# BBeams.net
KiCad netlist of a schematic drawn in Altium Designer
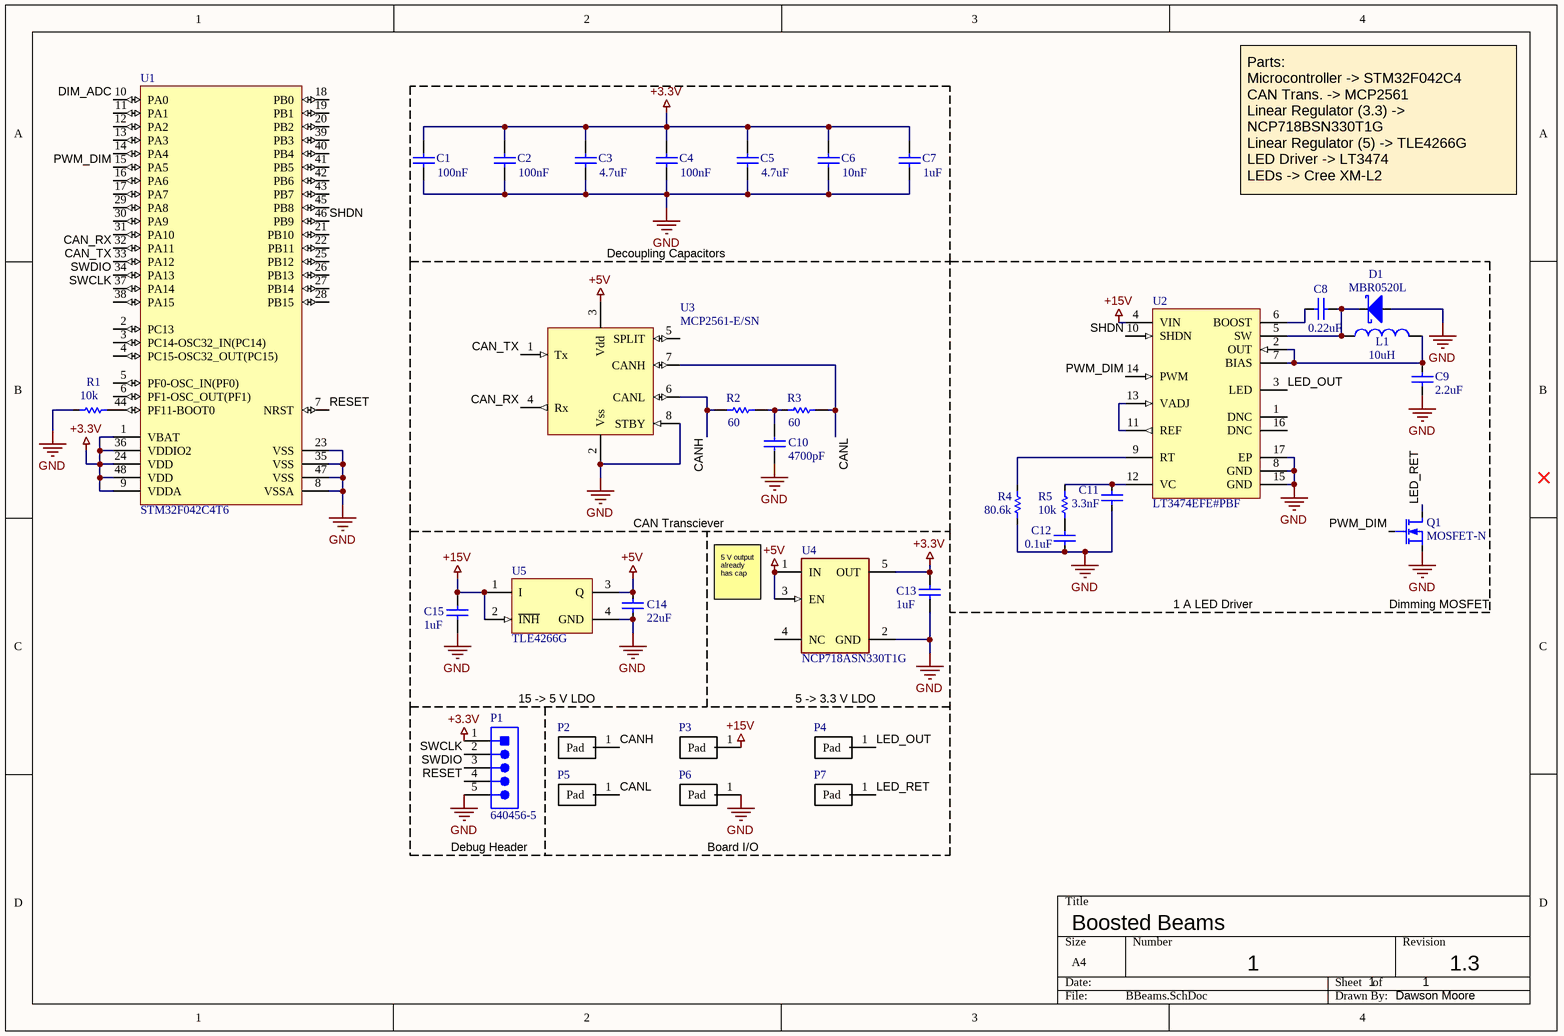
[diagram p0: BBeams.SchDoc]

(export (version "E")
  (design (tool "Eeschema 10.0.6"))
  (components
    (comp (ref "C1")
      (value "100nF")
      (footprint "1608[0603]")
      (description "Capacitor (Semiconductor SIM Model)")
      (fields (field (name "Comment") "Cap Semi") (field (name "PUBLISHER") "Altium Limited"))
      (libsource (lib "Miscellaneous Devices") (part "Cap Semi"))
    )
    (comp (ref "C2")
      (value "100nF")
      (footprint "1608[0603]")
      (description "Capacitor (Semiconductor SIM Model)")
      (fields (field (name "Comment") "Cap Semi") (field (name "PUBLISHER") "Altium Limited"))
      (libsource (lib "Miscellaneous Devices") (part "Cap Semi"))
    )
    (comp (ref "C3")
      (value "4.7uF")
      (footprint "1608[0603]")
      (description "Capacitor (Semiconductor SIM Model)")
      (fields (field (name "Comment") "Cap Semi") (field (name "PUBLISHER") "Altium Limited"))
      (libsource (lib "Miscellaneous Devices") (part "Cap Semi"))
    )
    (comp (ref "C4")
      (value "100nF")
      (footprint "1608[0603]")
      (description "Capacitor (Semiconductor SIM Model)")
      (fields (field (name "Comment") "Cap Semi") (field (name "PUBLISHER") "Altium Limited"))
      (libsource (lib "Miscellaneous Devices") (part "Cap Semi"))
    )
    (comp (ref "C5")
      (value "4.7uF")
      (footprint "1608[0603]")
      (description "Capacitor (Semiconductor SIM Model)")
      (fields (field (name "Comment") "Cap Semi") (field (name "PUBLISHER") "Altium Limited"))
      (libsource (lib "Miscellaneous Devices") (part "Cap Semi"))
    )
    (comp (ref "C6")
      (value "10nF")
      (footprint "1608[0603]")
      (description "Capacitor (Semiconductor SIM Model)")
      (fields (field (name "Comment") "Cap Semi") (field (name "PUBLISHER") "Altium Limited"))
      (libsource (lib "Miscellaneous Devices") (part "Cap Semi"))
    )
    (comp (ref "C7")
      (value "1uF")
      (footprint "1608[0603]")
      (description "Capacitor (Semiconductor SIM Model)")
      (fields (field (name "Comment") "Cap Semi") (field (name "PUBLISHER") "Altium Limited"))
      (libsource (lib "Miscellaneous Devices") (part "Cap Semi"))
    )
    (comp (ref "C8")
      (value "0.22uF")
      (footprint "1608[0603]")
      (description "Capacitor (Semiconductor SIM Model)")
      (fields (field (name "Comment") "Cap Semi") (field (name "PUBLISHER") "Altium Limited"))
      (libsource (lib "") (part "Cap Semi_1"))
    )
    (comp (ref "C9")
      (value "2.2uF")
      (footprint "1608[0603]")
      (description "Capacitor (Semiconductor SIM Model)")
      (fields (field (name "Comment") "Cap Semi") (field (name "PUBLISHER") "Altium Limited"))
      (libsource (lib "") (part "Cap Semi_1"))
    )
    (comp (ref "C10")
      (value "4700pF")
      (footprint "1608[0603]")
      (description "Capacitor (Semiconductor SIM Model)")
      (fields (field (name "Comment") "Cap Semi") (field (name "PUBLISHER") "Altium Limited"))
      (libsource (lib "Miscellaneous Devices") (part "Cap Semi"))
    )
    (comp (ref "C11")
      (value "3.3nF")
      (footprint "1608[0603]")
      (description "Capacitor (Semiconductor SIM Model)")
      (fields (field (name "Comment") "Cap Semi") (field (name "PUBLISHER") "Altium Limited"))
      (libsource (lib "") (part "Cap Semi_2"))
    )
    (comp (ref "C12")
      (value "0.1uF")
      (footprint "1608[0603]")
      (description "Capacitor (Semiconductor SIM Model)")
      (fields (field (name "Comment") "Cap Semi") (field (name "PUBLISHER") "Altium Limited"))
      (libsource (lib "") (part "Cap Semi_2"))
    )
    (comp (ref "C13")
      (value "1uF")
      (footprint "1608[0603]")
      (description "Capacitor (Semiconductor SIM Model)")
      (fields (field (name "Comment") "Cap Semi") (field (name "PUBLISHER") "Altium Limited"))
      (libsource (lib "Miscellaneous Devices") (part "Cap Semi"))
    )
    (comp (ref "C14")
      (value "22uF")
      (footprint "1608[0603]")
      (description "Capacitor (Semiconductor SIM Model)")
      (fields (field (name "Comment") "Cap Semi") (field (name "PUBLISHER") "Altium Limited"))
      (libsource (lib "") (part "Cap Semi_2"))
    )
    (comp (ref "C15")
      (value "1uF")
      (footprint "1608[0603]")
      (description "Capacitor (Semiconductor SIM Model)")
      (fields (field (name "Comment") "Cap Semi") (field (name "PUBLISHER") "Altium Limited"))
      (libsource (lib "Miscellaneous Devices") (part "Cap Semi"))
    )
    (comp (ref "D1")
      (value "MBR0520L")
      (footprint "ONSC-SOD-123-2-425-04_V")
      (description "Schottky Diode, 20V, 0.2A, 2-pin SOD-123, RoHS, Tape and Reel")
      (fields (field (name "MANUFACTURER") "FairchildSemiconductor"))
      (libsource (lib "Altium Content Vault") (part "DSKY-KA-2"))
    )
    (comp (ref "L1")
      (value "10uH")
      (footprint "1608[0603]")
      (description "Inductor")
      (fields (field (name "PUBLISHER") "Altium Limited"))
      (libsource (lib "Miscellaneous Devices") (part "Inductor"))
    )
    (comp (ref "P1")
      (value "640456-5")
      (footprint "TECO-640456-5")
      (fields (field (name "MANUFACTURER") "TE Connectivity"))
      (libsource (lib "Altium Content Vault") (part "CN-1P-M-R5"))
    )
    (comp (ref "P2") (value "I/O Pad") (footprint "I/O Pad") (libsource (lib "BBeams") (part "I/O Pad")))
    (comp (ref "P3") (value "I/O Pad") (footprint "I/O Pad") (libsource (lib "BBeams") (part "I/O Pad")))
    (comp (ref "P4") (value "I/O Pad") (footprint "I/O Pad") (libsource (lib "BBeams") (part "I/O Pad")))
    (comp (ref "P5") (value "I/O Pad") (footprint "I/O Pad") (libsource (lib "BBeams") (part "I/O Pad")))
    (comp (ref "P6") (value "I/O Pad") (footprint "I/O Pad") (libsource (lib "BBeams") (part "I/O Pad")))
    (comp (ref "P7") (value "I/O Pad") (footprint "I/O Pad") (libsource (lib "BBeams") (part "I/O Pad")))
    (comp (ref "Q1")
      (value "MOSFET-N")
      (footprint "SOT-23_N")
      (description "N-Channel MOSFET")
      (fields (field (name "PUBLISHER") "Altium Limited"))
      (libsource (lib "Miscellaneous Devices") (part "MOSFET-N"))
    )
    (comp (ref "R1")
      (value "10k")
      (footprint "1608[0603]")
      (description "Resistor")
      (fields (field (name "Comment") "Res1") (field (name "PUBLISHER") "Altium Limited"))
      (libsource (lib "") (part "Res1_1"))
    )
    (comp (ref "R2")
      (value "60")
      (footprint "1608[0603]")
      (description "Resistor")
      (fields (field (name "Comment") "Res1") (field (name "PUBLISHER") "Altium Limited"))
      (libsource (lib "Miscellaneous Devices") (part "Res1"))
    )
    (comp (ref "R3")
      (value "60")
      (footprint "1608[0603]")
      (description "Resistor")
      (fields (field (name "Comment") "Res1") (field (name "PUBLISHER") "Altium Limited"))
      (libsource (lib "Miscellaneous Devices") (part "Res1"))
    )
    (comp (ref "R4")
      (value "80.6k")
      (footprint "1608[0603]")
      (description "Resistor")
      (fields (field (name "Comment") "Res1") (field (name "PUBLISHER") "Altium Limited"))
      (libsource (lib "") (part "Res1_1"))
    )
    (comp (ref "R5")
      (value "10k")
      (footprint "1608[0603]")
      (description "Resistor")
      (fields (field (name "Comment") "Res1") (field (name "PUBLISHER") "Altium Limited"))
      (libsource (lib "") (part "Res1_1"))
    )
    (comp (ref "U1")
      (value "STM32F042C4T6")
      (footprint "STM-LQFP48_M")
      (fields (field (name "MANUFACTURER") "STMicroelectronics"))
      (libsource (lib "Altium Content Vault") (part "MC-ARM-STM32F042-LQFP48"))
    )
    (comp (ref "U2")
      (value "LT3474EFE#PBF")
      (footprint "LT-FE-16-EPV-BA_N")
      (fields (field (name "MANUFACTURER") "Linear Technology"))
      (libsource (lib "Altium Content Vault") (part "LT-LT3474-X-FE-16"))
    )
    (comp (ref "U3")
      (value "MCP2561-E/SN")
      (footprint "SO8_L")
      (libsource (lib "BBeams") (part "MCP2561-E/SN"))
    )
    (comp (ref "U4")
      (value "NCP718ASN330T1G")
      (footprint "FP-419AE-01-IPC_C")
      (description "300 MA LOW IQ WIDE INPUT")
      (fields
        (field (name "OCTOPART") "https://octopart.com/ncp718asn330t1g-on+semiconductor-87658778")
        (field (name "MANUFACTURER") "ON Semiconductor")
      )
      (libsource (lib "Altium Content Vault") (part "2c1d114799b120670ceedeac5567598"))
    )
    (comp (ref "U5")
      (value "TLE4266G")
      (footprint "INF-PG-SOT223_SC-73_N")
      (fields (field (name "MANUFACTURER") "Infineon"))
      (libsource (lib "Altium Content Vault") (part "INF-TLE4266X-SOT223(SC-73)-4"))
    )
  )
  (nets
    (net (code "1") (name "+3.3V") (class "Default")
      (node (ref "C1") (pin "2") (pinfunction "2_2") (pintype "passive"))
      (node (ref "C13") (pin "2") (pinfunction "2_2") (pintype "passive"))
      (node (ref "C2") (pin "2") (pinfunction "2_2") (pintype "passive"))
      (node (ref "C3") (pin "2") (pinfunction "2_2") (pintype "passive"))
      (node (ref "C4") (pin "2") (pinfunction "2_2") (pintype "passive"))
      (node (ref "C5") (pin "2") (pinfunction "2_2") (pintype "passive"))
      (node (ref "C6") (pin "2") (pinfunction "2_2") (pintype "passive"))
      (node (ref "C7") (pin "2") (pinfunction "2_2") (pintype "passive"))
      (node (ref "P1") (pin "1") (pinfunction "DTR_1") (pintype "passive"))
      (node (ref "U1") (pin "1") (pinfunction "VBAT_1") (pintype "power_in"))
      (node (ref "U1") (pin "24") (pinfunction "VDD_24") (pintype "power_in"))
      (node (ref "U1") (pin "36") (pinfunction "VDDIO2_36") (pintype "power_in"))
      (node (ref "U1") (pin "48") (pinfunction "VDD_48") (pintype "power_in"))
      (node (ref "U1") (pin "9") (pinfunction "VDDA_9") (pintype "power_in"))
      (node (ref "U4") (pin "5") (pinfunction "OUT_5") (pintype "power_in"))
    )
    (net (code "2") (name "+5V") (class "Default")
      (node (ref "C14") (pin "2") (pinfunction "2_2") (pintype "passive"))
      (node (ref "U3") (pin "3") (pinfunction "Vdd_3") (pintype "power_in"))
      (node (ref "U4") (pin "1") (pinfunction "IN_1") (pintype "power_in"))
      (node (ref "U4") (pin "3") (pinfunction "EN_3") (pintype "input"))
      (node (ref "U5") (pin "3") (pinfunction "Q_3") (pintype "power_in"))
    )
    (net (code "3") (name "+15V") (class "Default")
      (node (ref "C15") (pin "2") (pinfunction "2_2") (pintype "passive"))
      (node (ref "P3") (pin "1") (pinfunction "Pad_1") (pintype "passive"))
      (node (ref "U2") (pin "4") (pinfunction "VIN_4") (pintype "power_in"))
      (node (ref "U5") (pin "1") (pinfunction "I_1") (pintype "power_in"))
      (node (ref "U5") (pin "2") (pinfunction "~{INH}_2") (pintype "input"))
    )
    (net (code "4") (name "/CANH") (class "Default")
      (node (ref "P2") (pin "1") (pinfunction "Pad_1") (pintype "passive"))
      (node (ref "R2") (pin "1") (pinfunction "1_1") (pintype "passive"))
      (node (ref "U3") (pin "6") (pinfunction "CANL_6") (pintype "bidirectional"))
    )
    (net (code "5") (name "/CANL") (class "Default")
      (node (ref "P5") (pin "1") (pinfunction "Pad_1") (pintype "passive"))
      (node (ref "R3") (pin "2") (pinfunction "2_2") (pintype "passive"))
      (node (ref "U3") (pin "7") (pinfunction "CANH_7") (pintype "bidirectional"))
    )
    (net (code "6") (name "/CAN_RX") (class "Default")
      (node (ref "U1") (pin "32") (pinfunction "PA11_32") (pintype "bidirectional"))
      (node (ref "U3") (pin "4") (pinfunction "Rx_4") (pintype "output"))
    )
    (net (code "7") (name "/CAN_TX") (class "Default")
      (node (ref "U1") (pin "33") (pinfunction "PA12_33") (pintype "bidirectional"))
      (node (ref "U3") (pin "1") (pinfunction "Tx_1") (pintype "input"))
    )
    (net (code "8") (name "/LED_OUT") (class "Default")
      (node (ref "P4") (pin "1") (pinfunction "Pad_1") (pintype "passive"))
      (node (ref "U2") (pin "3") (pinfunction "LED_3") (pintype "power_in"))
    )
    (net (code "9") (name "/LED_RET") (class "Default")
      (node (ref "P7") (pin "1") (pinfunction "Pad_1") (pintype "passive"))
      (node (ref "Q1") (pin "1") (pinfunction "D_1") (pintype "passive"))
    )
    (net (code "10") (name "/PWM_DIM") (class "Default")
      (node (ref "Q1") (pin "2") (pinfunction "G_2") (pintype "passive"))
      (node (ref "U1") (pin "15") (pinfunction "PA5_15") (pintype "bidirectional"))
      (node (ref "U2") (pin "14") (pinfunction "PWM_14") (pintype "input"))
    )
    (net (code "11") (name "/RESET") (class "Default")
      (node (ref "P1") (pin "4") (pinfunction "VCC_4") (pintype "passive"))
      (node (ref "U1") (pin "7") (pinfunction "NRST_7") (pintype "bidirectional"))
    )
    (net (code "12") (name "/SHDN") (class "Default")
      (node (ref "U1") (pin "46") (pinfunction "PB9_46") (pintype "bidirectional"))
      (node (ref "U2") (pin "10") (pinfunction "SHDN_10") (pintype "input"))
    )
    (net (code "13") (name "/SWCLK") (class "Default")
      (node (ref "P1") (pin "2") (pinfunction "RXI_2") (pintype "passive"))
      (node (ref "U1") (pin "37") (pinfunction "PA14_37") (pintype "bidirectional"))
    )
    (net (code "14") (name "/SWDIO") (class "Default")
      (node (ref "P1") (pin "3") (pinfunction "TXO_3") (pintype "passive"))
      (node (ref "U1") (pin "34") (pinfunction "PA13_34") (pintype "bidirectional"))
    )
    (net (code "15") (name "GND") (class "Default")
      (node (ref "C1") (pin "1") (pinfunction "1_1") (pintype "passive"))
      (node (ref "C10") (pin "1") (pinfunction "1_1") (pintype "passive"))
      (node (ref "C11") (pin "1") (pinfunction "1_1") (pintype "passive"))
      (node (ref "C12") (pin "1") (pinfunction "1_1") (pintype "passive"))
      (node (ref "C13") (pin "1") (pinfunction "1_1") (pintype "passive"))
      (node (ref "C14") (pin "1") (pinfunction "1_1") (pintype "passive"))
      (node (ref "C15") (pin "1") (pinfunction "1_1") (pintype "passive"))
      (node (ref "C2") (pin "1") (pinfunction "1_1") (pintype "passive"))
      (node (ref "C3") (pin "1") (pinfunction "1_1") (pintype "passive"))
      (node (ref "C4") (pin "1") (pinfunction "1_1") (pintype "passive"))
      (node (ref "C5") (pin "1") (pinfunction "1_1") (pintype "passive"))
      (node (ref "C6") (pin "1") (pinfunction "1_1") (pintype "passive"))
      (node (ref "C7") (pin "1") (pinfunction "1_1") (pintype "passive"))
      (node (ref "C9") (pin "2") (pinfunction "2_2") (pintype "passive"))
      (node (ref "D1") (pin "2") (pinfunction "A_2") (pintype "passive"))
      (node (ref "P1") (pin "5") (pinfunction "CTS_5") (pintype "passive"))
      (node (ref "P6") (pin "1") (pinfunction "Pad_1") (pintype "passive"))
      (node (ref "Q1") (pin "3") (pinfunction "S_3") (pintype "passive"))
      (node (ref "R1") (pin "2") (pinfunction "2_2") (pintype "passive"))
      (node (ref "R4") (pin "1") (pinfunction "1_1") (pintype "passive"))
      (node (ref "U1") (pin "23") (pinfunction "VSS_23") (pintype "power_in"))
      (node (ref "U1") (pin "35") (pinfunction "VSS_35") (pintype "power_in"))
      (node (ref "U1") (pin "47") (pinfunction "VSS_47") (pintype "power_in"))
      (node (ref "U1") (pin "8") (pinfunction "VSSA_8") (pintype "power_in"))
      (node (ref "U2") (pin "15") (pinfunction "GND_15") (pintype "power_in"))
      (node (ref "U2") (pin "17") (pinfunction "EP_17") (pintype "power_in"))
      (node (ref "U2") (pin "8") (pinfunction "GND_8") (pintype "power_in"))
      (node (ref "U3") (pin "2") (pinfunction "Vss_2") (pintype "power_in"))
      (node (ref "U3") (pin "8") (pinfunction "STBY_8") (pintype "input"))
      (node (ref "U4") (pin "2") (pinfunction "GND_2") (pintype "power_in"))
      (node (ref "U5") (pin "4") (pinfunction "GND_4") (pintype "power_in"))
    )
    (net (code "16") (name "Net-(C10-Pad2)") (class "Default")
      (node (ref "C10") (pin "2") (pinfunction "2_2") (pintype "passive"))
      (node (ref "R2") (pin "2") (pinfunction "2_2") (pintype "passive"))
      (node (ref "R3") (pin "1") (pinfunction "1_1") (pintype "passive"))
    )
    (net (code "17") (name "Net-(C12-Pad2)") (class "Default")
      (node (ref "C12") (pin "2") (pinfunction "2_2") (pintype "passive"))
      (node (ref "R5") (pin "1") (pinfunction "1_1") (pintype "passive"))
    )
    (net (code "18") (name "Net-(D1-K)") (class "Default")
      (node (ref "C8") (pin "1") (pinfunction "1_1") (pintype "passive"))
      (node (ref "D1") (pin "1") (pinfunction "K_1") (pintype "passive"))
      (node (ref "L1") (pin "1") (pinfunction "1_1") (pintype "passive"))
      (node (ref "U2") (pin "5") (pinfunction "SW_5") (pintype "power_in"))
    )
    (net (code "19") (name "Net-(U1-PF11-BOOT0)") (class "Default")
      (node (ref "R1") (pin "1") (pinfunction "1_1") (pintype "passive"))
      (node (ref "U1") (pin "44") (pinfunction "PF11-BOOT0_44") (pintype "bidirectional"))
    )
    (net (code "20") (name "Net-(U2-BIAS)") (class "Default")
      (node (ref "C9") (pin "1") (pinfunction "1_1") (pintype "passive"))
      (node (ref "L1") (pin "2") (pinfunction "2_2") (pintype "passive"))
      (node (ref "U2") (pin "2") (pinfunction "OUT_2") (pintype "input"))
      (node (ref "U2") (pin "7") (pinfunction "BIAS_7") (pintype "power_in"))
    )
    (net (code "21") (name "Net-(U2-BOOST)") (class "Default")
      (node (ref "C8") (pin "2") (pinfunction "2_2") (pintype "passive"))
      (node (ref "U2") (pin "6") (pinfunction "BOOST_6") (pintype "passive"))
    )
    (net (code "22") (name "Net-(U2-REF)") (class "Default")
      (node (ref "U2") (pin "11") (pinfunction "REF_11") (pintype "output"))
      (node (ref "U2") (pin "13") (pinfunction "VADJ_13") (pintype "input"))
    )
    (net (code "23") (name "Net-(U2-RT)") (class "Default")
      (node (ref "R4") (pin "2") (pinfunction "2_2") (pintype "passive"))
      (node (ref "U2") (pin "9") (pinfunction "RT_9") (pintype "passive"))
    )
    (net (code "24") (name "Net-(U2-VC)") (class "Default")
      (node (ref "C11") (pin "2") (pinfunction "2_2") (pintype "passive"))
      (node (ref "R5") (pin "2") (pinfunction "2_2") (pintype "passive"))
      (node (ref "U2") (pin "12") (pinfunction "VC_12") (pintype "passive"))
    )
    (net (code "25") (name "unconnected-(U1-PA0-Pad10)") (class "Default")
      (node (ref "U1") (pin "10") (pinfunction "PA0_10") (pintype "bidirectional"))
    )
    (net (code "26") (name "unconnected-(U1-PA1-Pad11)") (class "Default")
      (node (ref "U1") (pin "11") (pinfunction "PA1_11") (pintype "bidirectional"))
    )
    (net (code "27") (name "unconnected-(U1-PA2-Pad12)") (class "Default")
      (node (ref "U1") (pin "12") (pinfunction "PA2_12") (pintype "bidirectional"))
    )
    (net (code "28") (name "unconnected-(U1-PA3-Pad13)") (class "Default")
      (node (ref "U1") (pin "13") (pinfunction "PA3_13") (pintype "bidirectional"))
    )
    (net (code "29") (name "unconnected-(U1-PA4-Pad14)") (class "Default")
      (node (ref "U1") (pin "14") (pinfunction "PA4_14") (pintype "bidirectional"))
    )
    (net (code "30") (name "unconnected-(U1-PA6-Pad16)") (class "Default")
      (node (ref "U1") (pin "16") (pinfunction "PA6_16") (pintype "bidirectional"))
    )
    (net (code "31") (name "unconnected-(U1-PA7-Pad17)") (class "Default")
      (node (ref "U1") (pin "17") (pinfunction "PA7_17") (pintype "bidirectional"))
    )
    (net (code "32") (name "unconnected-(U1-PA8-Pad29)") (class "Default")
      (node (ref "U1") (pin "29") (pinfunction "PA8_29") (pintype "bidirectional"))
    )
    (net (code "33") (name "unconnected-(U1-PA9-Pad30)") (class "Default")
      (node (ref "U1") (pin "30") (pinfunction "PA9_30") (pintype "bidirectional"))
    )
    (net (code "34") (name "unconnected-(U1-PA10-Pad31)") (class "Default")
      (node (ref "U1") (pin "31") (pinfunction "PA10_31") (pintype "bidirectional"))
    )
    (net (code "35") (name "unconnected-(U1-PA15-Pad38)") (class "Default")
      (node (ref "U1") (pin "38") (pinfunction "PA15_38") (pintype "bidirectional"))
    )
    (net (code "36") (name "unconnected-(U1-PB0-Pad18)") (class "Default")
      (node (ref "U1") (pin "18") (pinfunction "PB0_18") (pintype "bidirectional"))
    )
    (net (code "37") (name "unconnected-(U1-PB1-Pad19)") (class "Default")
      (node (ref "U1") (pin "19") (pinfunction "PB1_19") (pintype "bidirectional"))
    )
    (net (code "38") (name "unconnected-(U1-PB2-Pad20)") (class "Default")
      (node (ref "U1") (pin "20") (pinfunction "PB2_20") (pintype "bidirectional"))
    )
    (net (code "39") (name "unconnected-(U1-PB3-Pad39)") (class "Default")
      (node (ref "U1") (pin "39") (pinfunction "PB3_39") (pintype "bidirectional"))
    )
    (net (code "40") (name "unconnected-(U1-PB4-Pad40)") (class "Default")
      (node (ref "U1") (pin "40") (pinfunction "PB4_40") (pintype "bidirectional"))
    )
    (net (code "41") (name "unconnected-(U1-PB5-Pad41)") (class "Default")
      (node (ref "U1") (pin "41") (pinfunction "PB5_41") (pintype "bidirectional"))
    )
    (net (code "42") (name "unconnected-(U1-PB6-Pad42)") (class "Default")
      (node (ref "U1") (pin "42") (pinfunction "PB6_42") (pintype "bidirectional"))
    )
    (net (code "43") (name "unconnected-(U1-PB7-Pad43)") (class "Default")
      (node (ref "U1") (pin "43") (pinfunction "PB7_43") (pintype "bidirectional"))
    )
    (net (code "44") (name "unconnected-(U1-PB8-Pad45)") (class "Default")
      (node (ref "U1") (pin "45") (pinfunction "PB8_45") (pintype "bidirectional"))
    )
    (net (code "45") (name "unconnected-(U1-PB10-Pad21)") (class "Default")
      (node (ref "U1") (pin "21") (pinfunction "PB10_21") (pintype "bidirectional"))
    )
    (net (code "46") (name "unconnected-(U1-PB11-Pad22)") (class "Default")
      (node (ref "U1") (pin "22") (pinfunction "PB11_22") (pintype "bidirectional"))
    )
    (net (code "47") (name "unconnected-(U1-PB12-Pad25)") (class "Default")
      (node (ref "U1") (pin "25") (pinfunction "PB12_25") (pintype "bidirectional"))
    )
    (net (code "48") (name "unconnected-(U1-PB13-Pad26)") (class "Default")
      (node (ref "U1") (pin "26") (pinfunction "PB13_26") (pintype "bidirectional"))
    )
    (net (code "49") (name "unconnected-(U1-PB14-Pad27)") (class "Default")
      (node (ref "U1") (pin "27") (pinfunction "PB14_27") (pintype "bidirectional"))
    )
    (net (code "50") (name "unconnected-(U1-PB15-Pad28)") (class "Default")
      (node (ref "U1") (pin "28") (pinfunction "PB15_28") (pintype "bidirectional"))
    )
    (net (code "51") (name "unconnected-(U1-PC13-Pad2)") (class "Default")
      (node (ref "U1") (pin "2") (pinfunction "PC13_2") (pintype "bidirectional"))
    )
    (net (code "52") (name "unconnected-(U1-PC14-OSC32_IN(PC14)-Pad3)") (class "Default")
      (node (ref "U1") (pin "3") (pinfunction "PC14-OSC32_IN(PC14)_3") (pintype "bidirectional"))
    )
    (net (code "53") (name "unconnected-(U1-PC15-OSC32_OUT(PC15)-Pad4)") (class "Default")
      (node (ref "U1") (pin "4") (pinfunction "PC15-OSC32_OUT(PC15)_4") (pintype "bidirectional"))
    )
    (net (code "54") (name "unconnected-(U1-PF0-OSC_IN(PF0)-Pad5)") (class "Default")
      (node (ref "U1") (pin "5") (pinfunction "PF0-OSC_IN(PF0)_5") (pintype "bidirectional"))
    )
    (net (code "55") (name "unconnected-(U1-PF1-OSC_OUT(PF1)-Pad6)") (class "Default")
      (node (ref "U1") (pin "6") (pinfunction "PF1-OSC_OUT(PF1)_6") (pintype "bidirectional"))
    )
    (net (code "56") (name "unconnected-(U2-DNC-Pad1)") (class "Default")
      (node (ref "U2") (pin "1") (pinfunction "DNC_1") (pintype "passive"))
    )
    (net (code "57") (name "unconnected-(U2-DNC-Pad16)") (class "Default")
      (node (ref "U2") (pin "16") (pinfunction "DNC_16") (pintype "passive"))
    )
    (net (code "58") (name "unconnected-(U3-SPLIT-Pad5)") (class "Default")
      (node (ref "U3") (pin "5") (pinfunction "SPLIT_5") (pintype "bidirectional"))
    )
    (net (code "59") (name "unconnected-(U4-NC-Pad4)") (class "Default")
      (node (ref "U4") (pin "4") (pinfunction "NC_4") (pintype "passive"))
    )
  )
)
